# LOADCELL_SCH.net
KiCad netlist of a schematic drawn in Altium Designer
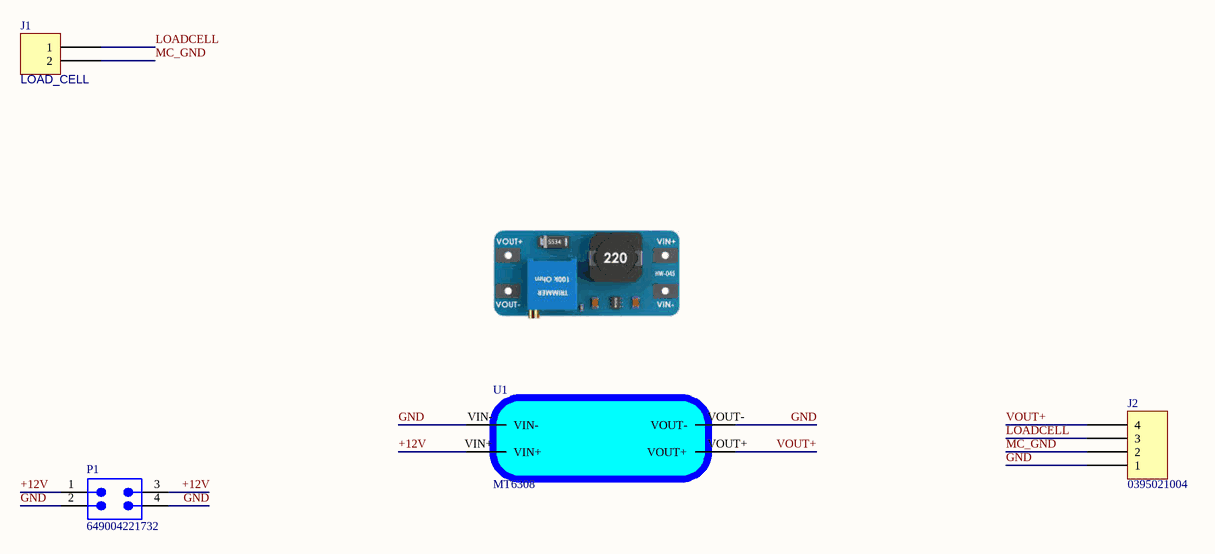
[diagram p0: LOADCELL_SCH.SchDoc]

(export (version "E")
  (design (tool "Eeschema 10.0.6"))
  (components
    (comp (ref "J1")
      (value "LOAD_CELL")
      (footprint "SAMTEC SSW-102-03-T-S")
      (description "CONN RCPT 2POS 0.1 TIN PCB")
      (fields (field (name "PART NUMBER") "SSW-102-03-T-S") (field (name "MANUFACTURER") "Samtec Inc."))
      (libsource (lib "Celestial Altium Library - altium_library") (part "2 Pin"))
    )
    (comp (ref "J2")
      (value "0395021004")
      (footprint "MOLEX 395021004")
      (description "TERM BLOCK HDR 4POS 90DEG 3.5MM")
      (fields (field (name "MANUFACTURER") "Molex"))
      (libsource (lib "Celestial Altium Library - altium_library") (part "4 Pin"))
    )
    (comp (ref "P1")
      (value "649004221732")
      (footprint "649004221732")
      (libsource (lib "Altium Content Vault") (part "Header_Male_2R_04P(A)"))
    )
    (comp (ref "U1") (value "MT6308") (footprint "PCBComponent_1") (libsource (lib "MT6308") (part "U")))
  )
  (nets
    (net (code "1") (name "/+12V") (class "Default")
      (node (ref "P1") (pin "1") (pinfunction "1_1") (pintype "passive"))
      (node (ref "P1") (pin "3") (pinfunction "3_3") (pintype "passive"))
      (node (ref "U1") (pin "VIN+") (pinfunction "VIN+_VIN+") (pintype "passive"))
    )
    (net (code "2") (name "/GND") (class "Default")
      (node (ref "J2") (pin "1") (pinfunction "1_1") (pintype "passive"))
      (node (ref "P1") (pin "2") (pinfunction "2_2") (pintype "passive"))
      (node (ref "P1") (pin "4") (pinfunction "4_4") (pintype "passive"))
      (node (ref "U1") (pin "VIN-") (pinfunction "VIN-_VIN-") (pintype "passive"))
      (node (ref "U1") (pin "VOUT-") (pinfunction "VOUT-_VOUT-") (pintype "passive"))
    )
    (net (code "3") (name "/LOADCELL") (class "Default")
      (node (ref "J1") (pin "1") (pinfunction "1_1") (pintype "passive"))
      (node (ref "J2") (pin "3") (pinfunction "3_3") (pintype "passive"))
    )
    (net (code "4") (name "/MC_GND") (class "Default")
      (node (ref "J1") (pin "2") (pinfunction "2_2") (pintype "passive"))
      (node (ref "J2") (pin "2") (pinfunction "2_2") (pintype "passive"))
    )
    (net (code "5") (name "/VOUT+") (class "Default")
      (node (ref "J2") (pin "4") (pinfunction "4_4") (pintype "passive"))
      (node (ref "U1") (pin "VOUT+") (pinfunction "VOUT+_VOUT+") (pintype "passive"))
    )
  )
)
